# APA102_Arduino.net
KiCad netlist of a schematic drawn in EAGLE
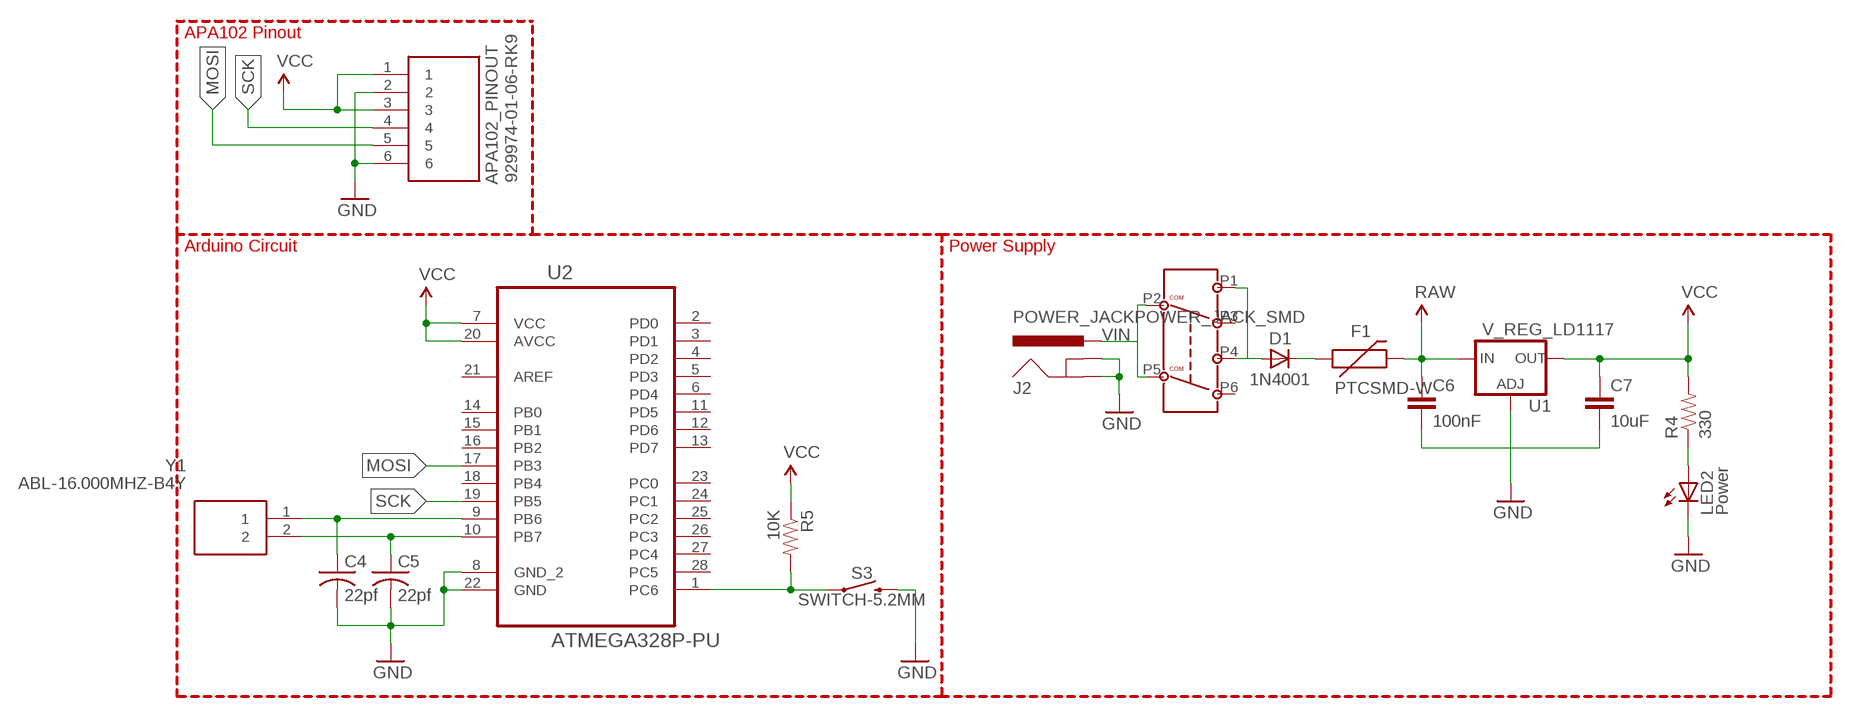
[diagram p0: schematic, sheet 1]

(export (version "E")
  (design (tool "Eeschema 10.0.6"))
  (components
    (comp (ref "APA102_PINOUT")
      (value "929974-01-06-RK9")
      (footprint "eagle-import:929974-01-06-RK")
      (libsource (lib "eagle-import") (part "929974-01-06-RK929974-01-06-RK"))
    )
    (comp (ref "C4")
      (value "22pf")
      (footprint "eagle-import:C0805")
      (libsource (lib "eagle-import") (part "C-USC0805"))
    )
    (comp (ref "C5")
      (value "22pf")
      (footprint "eagle-import:C0805")
      (libsource (lib "eagle-import") (part "C-USC0805"))
    )
    (comp (ref "C6")
      (value "100nF")
      (footprint "eagle-import:0603-CAP")
      (libsource (lib "eagle-import") (part "CAP0603-CAP"))
    )
    (comp (ref "C7")
      (value "10uF")
      (footprint "eagle-import:0603-CAP")
      (libsource (lib "eagle-import") (part "CAP0603-CAP"))
    )
    (comp (ref "D1")
      (value "1N4001")
      (footprint "eagle-import:DO41-10")
      (libsource (lib "eagle-import") (part "1N4004"))
    )
    (comp (ref "F1")
      (value "PTCSMD-W")
      (footprint "eagle-import:PTC-1206-WIDE")
      (libsource (lib "eagle-import") (part "PTCSMD-W"))
    )
    (comp (ref "J2")
      (value "POWER_JACKPOWER_JACK_SMD")
      (footprint "eagle-import:POWER_JACK_SMD")
      (libsource (lib "eagle-import") (part "POWER_JACKPOWER_JACK_SMD"))
    )
    (comp (ref "LED2")
      (value "Power")
      (footprint "eagle-import:LED-1206")
      (libsource (lib "eagle-import") (part "LED1206"))
    )
    (comp (ref "POWER_SWITCH")
      (value "6-PIN-SLIDE-SWITCH")
      (footprint "eagle-import:6-PIN-SLIDE-SWITCH")
      (libsource (lib "eagle-import") (part "6-PIN-SLIDE-SWITCH"))
    )
    (comp (ref "R4")
      (value "330")
      (footprint "eagle-import:0603-RES")
      (libsource (lib "eagle-import") (part "RESISTOR0603-RES"))
    )
    (comp (ref "R5")
      (value "10K")
      (footprint "eagle-import:0603-RES")
      (libsource (lib "eagle-import") (part "RESISTOR0603-RES"))
    )
    (comp (ref "S3")
      (value "SWITCH-5.2MM")
      (footprint "eagle-import:TACTILE_SWITCH_SMD_5.2MM")
      (libsource (lib "eagle-import") (part "MOMENTARY-SWITCH-SPST-SMD-5.2MM"))
    )
    (comp (ref "U1")
      (value "V_REG_LD1117")
      (footprint "eagle-import:SOT223")
      (libsource (lib "eagle-import") (part "V_REG_317SMD"))
    )
    (comp (ref "U2")
      (value "ATMEGA328P-PU")
      (footprint "eagle-import:DIP254P762X457-28")
      (fields (field (name "MF") "Microchip"))
      (libsource (lib "eagle-import") (part "ATMEGA328P-PU"))
    )
    (comp (ref "Y1")
      (value "ABL-16.000MHZ-B4Y")
      (footprint "eagle-import:HC_49US_(AT49)PTH")
      (fields
        (field (name "MANUFACTURER_PART_NUMBER") "ABL-16.000MHz-B4Y")
        (field (name "MOUSER_PART_NUMBER") "815-ABL-16-B4Y")
      )
      (libsource (lib "eagle-import") (part "ABL-16.000MHZ-B4Y"))
    )
  )
  (nets
    (net (code "1") (name "/VIN") (class "Default")
      (node (ref "J2") (pin "VIN0") (pinfunction "PWR_VIN0") (pintype "bidirectional"))
      (node (ref "POWER_SWITCH") (pin "P2") (pinfunction "2_P2") (pintype "bidirectional"))
      (node (ref "POWER_SWITCH") (pin "P5") (pinfunction "5_P5") (pintype "bidirectional"))
    )
    (net (code "2") (name "GND") (class "Default")
      (node (ref "APA102_PINOUT") (pin "2") (pinfunction "2_2") (pintype "bidirectional"))
      (node (ref "APA102_PINOUT") (pin "6") (pinfunction "6_6") (pintype "bidirectional"))
      (node (ref "C4") (pin "2") (pinfunction "2_2") (pintype "passive"))
      (node (ref "C5") (pin "2") (pinfunction "2_2") (pintype "passive"))
      (node (ref "C6") (pin "2") (pinfunction "2_2") (pintype "passive"))
      (node (ref "C7") (pin "2") (pinfunction "2_2") (pintype "passive"))
      (node (ref "J2") (pin "GND") (pinfunction "GND_GND") (pintype "bidirectional"))
      (node (ref "J2") (pin "P$4") (pinfunction "GNDBREAK_P$4") (pintype "bidirectional"))
      (node (ref "LED2") (pin "C") (pinfunction "C_C") (pintype "passive"))
      (node (ref "S3") (pin "3") (pinfunction "2_3") (pintype "passive"))
      (node (ref "U1") (pin "1") (pinfunction "ADJ_1") (pintype "input"))
      (node (ref "U2") (pin "22") (pinfunction "GND_22") (pintype "passive"))
      (node (ref "U2") (pin "8") (pinfunction "GND_2_8") (pintype "passive"))
    )
    (net (code "3") (name "MOSI") (class "Default")
      (node (ref "APA102_PINOUT") (pin "5") (pinfunction "5_5") (pintype "bidirectional"))
      (node (ref "U2") (pin "17") (pinfunction "PB3_17") (pintype "bidirectional"))
    )
    (net (code "4") (name "Net-(D1-PadC)") (class "Default")
      (node (ref "D1") (pin "C") (pinfunction "C_C") (pintype "passive"))
      (node (ref "F1") (pin "1") (pinfunction "1_1") (pintype "bidirectional"))
    )
    (net (code "5") (name "Net-(LED2-PadA)") (class "Default")
      (node (ref "LED2") (pin "A") (pinfunction "A_A") (pintype "passive"))
      (node (ref "R4") (pin "1") (pinfunction "1_1") (pintype "passive"))
    )
    (net (code "6") (name "Net-(POWER_SWITCH-1)") (class "Default")
      (node (ref "D1") (pin "A") (pinfunction "A_A") (pintype "passive"))
      (node (ref "POWER_SWITCH") (pin "P1") (pinfunction "1_P1") (pintype "bidirectional"))
      (node (ref "POWER_SWITCH") (pin "P4") (pinfunction "4_P4") (pintype "bidirectional"))
    )
    (net (code "7") (name "Net-(U2-PB6)") (class "Default")
      (node (ref "C4") (pin "1") (pinfunction "1_1") (pintype "passive"))
      (node (ref "U2") (pin "9") (pinfunction "PB6_9") (pintype "bidirectional"))
      (node (ref "Y1") (pin "1") (pinfunction "1_1") (pintype "bidirectional"))
    )
    (net (code "8") (name "Net-(U2-PB7)") (class "Default")
      (node (ref "C5") (pin "1") (pinfunction "1_1") (pintype "passive"))
      (node (ref "U2") (pin "10") (pinfunction "PB7_10") (pintype "bidirectional"))
      (node (ref "Y1") (pin "2") (pinfunction "2_2") (pintype "bidirectional"))
    )
    (net (code "9") (name "Net-(U2-PC6)") (class "Default")
      (node (ref "R5") (pin "2") (pinfunction "2_2") (pintype "passive"))
      (node (ref "S3") (pin "1") (pinfunction "1_1") (pintype "passive"))
      (node (ref "U2") (pin "1") (pinfunction "PC6_1") (pintype "bidirectional"))
    )
    (net (code "10") (name "RAW") (class "Default")
      (node (ref "C6") (pin "1") (pinfunction "1_1") (pintype "passive"))
      (node (ref "F1") (pin "2") (pinfunction "2_2") (pintype "bidirectional"))
      (node (ref "U1") (pin "3") (pinfunction "IN_3") (pintype "input"))
    )
    (net (code "11") (name "SCK") (class "Default")
      (node (ref "APA102_PINOUT") (pin "4") (pinfunction "4_4") (pintype "bidirectional"))
      (node (ref "U2") (pin "19") (pinfunction "PB5_19") (pintype "bidirectional"))
    )
    (net (code "12") (name "VCC") (class "Default")
      (node (ref "APA102_PINOUT") (pin "1") (pinfunction "1_1") (pintype "bidirectional"))
      (node (ref "APA102_PINOUT") (pin "3") (pinfunction "3_3") (pintype "bidirectional"))
      (node (ref "C7") (pin "1") (pinfunction "1_1") (pintype "passive"))
      (node (ref "R4") (pin "2") (pinfunction "2_2") (pintype "passive"))
      (node (ref "R5") (pin "1") (pinfunction "1_1") (pintype "passive"))
      (node (ref "U1") (pin "2") (pinfunction "OUT_2") (pintype "output"))
      (node (ref "U2") (pin "20") (pinfunction "AVCC_20") (pintype "power_in"))
      (node (ref "U2") (pin "7") (pinfunction "VCC_7") (pintype "power_in"))
    )
    (net (code "13") (name "unconnected-(POWER_SWITCH-3-PadP3)") (class "Default")
      (node (ref "POWER_SWITCH") (pin "P3") (pinfunction "3_P3") (pintype "bidirectional"))
    )
    (net (code "14") (name "unconnected-(POWER_SWITCH-6-PadP6)") (class "Default")
      (node (ref "POWER_SWITCH") (pin "P6") (pinfunction "6_P6") (pintype "bidirectional"))
    )
    (net (code "15") (name "unconnected-(U2-AREF-Pad21)") (class "Default")
      (node (ref "U2") (pin "21") (pinfunction "AREF_21") (pintype "input"))
    )
    (net (code "16") (name "unconnected-(U2-PB0-Pad14)") (class "Default")
      (node (ref "U2") (pin "14") (pinfunction "PB0_14") (pintype "bidirectional"))
    )
    (net (code "17") (name "unconnected-(U2-PB1-Pad15)") (class "Default")
      (node (ref "U2") (pin "15") (pinfunction "PB1_15") (pintype "bidirectional"))
    )
    (net (code "18") (name "unconnected-(U2-PB2-Pad16)") (class "Default")
      (node (ref "U2") (pin "16") (pinfunction "PB2_16") (pintype "bidirectional"))
    )
    (net (code "19") (name "unconnected-(U2-PB4-Pad18)") (class "Default")
      (node (ref "U2") (pin "18") (pinfunction "PB4_18") (pintype "bidirectional"))
    )
    (net (code "20") (name "unconnected-(U2-PC0-Pad23)") (class "Default")
      (node (ref "U2") (pin "23") (pinfunction "PC0_23") (pintype "bidirectional"))
    )
    (net (code "21") (name "unconnected-(U2-PC1-Pad24)") (class "Default")
      (node (ref "U2") (pin "24") (pinfunction "PC1_24") (pintype "bidirectional"))
    )
    (net (code "22") (name "unconnected-(U2-PC2-Pad25)") (class "Default")
      (node (ref "U2") (pin "25") (pinfunction "PC2_25") (pintype "bidirectional"))
    )
    (net (code "23") (name "unconnected-(U2-PC3-Pad26)") (class "Default")
      (node (ref "U2") (pin "26") (pinfunction "PC3_26") (pintype "bidirectional"))
    )
    (net (code "24") (name "unconnected-(U2-PC4-Pad27)") (class "Default")
      (node (ref "U2") (pin "27") (pinfunction "PC4_27") (pintype "bidirectional"))
    )
    (net (code "25") (name "unconnected-(U2-PC5-Pad28)") (class "Default")
      (node (ref "U2") (pin "28") (pinfunction "PC5_28") (pintype "bidirectional"))
    )
    (net (code "26") (name "unconnected-(U2-PD0-Pad2)") (class "Default")
      (node (ref "U2") (pin "2") (pinfunction "PD0_2") (pintype "bidirectional"))
    )
    (net (code "27") (name "unconnected-(U2-PD1-Pad3)") (class "Default")
      (node (ref "U2") (pin "3") (pinfunction "PD1_3") (pintype "bidirectional"))
    )
    (net (code "28") (name "unconnected-(U2-PD2-Pad4)") (class "Default")
      (node (ref "U2") (pin "4") (pinfunction "PD2_4") (pintype "bidirectional"))
    )
    (net (code "29") (name "unconnected-(U2-PD3-Pad5)") (class "Default")
      (node (ref "U2") (pin "5") (pinfunction "PD3_5") (pintype "bidirectional"))
    )
    (net (code "30") (name "unconnected-(U2-PD4-Pad6)") (class "Default")
      (node (ref "U2") (pin "6") (pinfunction "PD4_6") (pintype "bidirectional"))
    )
    (net (code "31") (name "unconnected-(U2-PD5-Pad11)") (class "Default")
      (node (ref "U2") (pin "11") (pinfunction "PD5_11") (pintype "bidirectional"))
    )
    (net (code "32") (name "unconnected-(U2-PD6-Pad12)") (class "Default")
      (node (ref "U2") (pin "12") (pinfunction "PD6_12") (pintype "bidirectional"))
    )
    (net (code "33") (name "unconnected-(U2-PD7-Pad13)") (class "Default")
      (node (ref "U2") (pin "13") (pinfunction "PD7_13") (pintype "bidirectional"))
    )
  )
)
